# M.net
KiCad netlist of a schematic drawn in Altium Designer
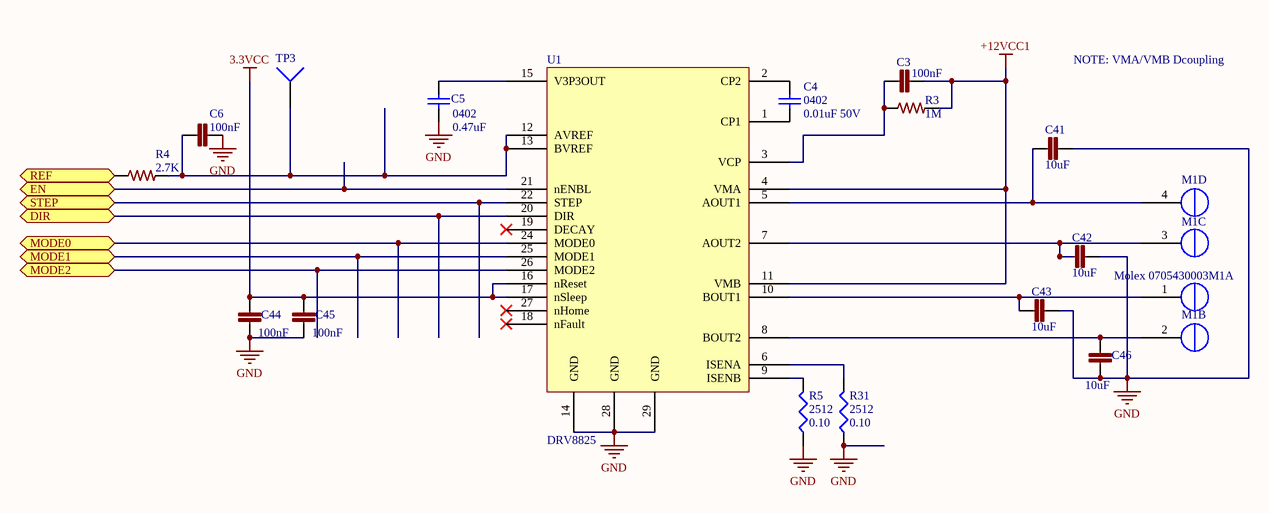
[diagram p0: M.SchDoc]

(export (version "E")
  (design (tool "Eeschema 10.0.6"))
  (components
    (comp (ref "C3")
      (value "100nF")
      (footprint "C0603")
      (description "CAP CER 0603 100nF 50V 10% X7R")
      (fields
        (field (name "MANUFACTURERPARTNUMBER") "C0603C104K5RACTU")
        (field (name "PUBLISHER") "UltiMachine")
      )
      (libsource (lib "3Delight") (part "C0603C104K5RACTU"))
    )
    (comp (ref "C4")
      (value "0.01uF 50V")
      (footprint "C0402")
      (description "CAP CER 10000PF 50V X7R 0402")
      (fields
        (field (name "MFR PART #") "GRM155R71H103JA88D")
        (field (name "MFR") "Murata")
        (field (name "PACKAGEREFERENCE") "0402")
        (field (name "PUBLISHER") "Ultimachine")
      )
      (libsource (lib "Tigershark3D") (part "GRM155R71H103JA88D"))
    )
    (comp (ref "C5")
      (value "0.47uF")
      (footprint "C0402")
      (description "0.47uF 6.3v C0402 - GRM155R60J474KE19D")
      (fields
        (field (name "MFR PART #") "GRM155R60J474KE19D")
        (field (name "MFR") "Murata")
        (field (name "PACKAGEREFERENCE") "0402")
        (field (name "PUBLISHER") "Ultimachine")
      )
      (libsource (lib "Tigershark3D") (part "GRM155R60J474KE19D"))
    )
    (comp (ref "C6")
      (value "100nF")
      (footprint "C0402")
      (description "CAP CER 0402 100nF 16V 10% X7R")
      (fields
        (field (name "MANUFACTURERPARTNUMBER") "GRM155R71C104KA88D")
        (field (name "PUBLISHER") "UltiMachine")
      )
      (libsource (lib "") (part "GRM155R71C104KA88D_1"))
    )
    (comp (ref "C41")
      (value "10uF")
      (footprint "C0603")
      (description "CAP CER 0603 1uF 10V Y5V")
      (fields
        (field (name "MANUFACTURERPARTNUMBER") "CC0603ZRY5V6BB105")
        (field (name "PUBLISHER") "UltiMachine")
      )
      (libsource (lib "Tigershark3D") (part "CC0603ZRY5V6BB105"))
    )
    (comp (ref "C42")
      (value "10uF")
      (footprint "C0603")
      (description "CAP CER 0603 1uF 10V Y5V")
      (fields
        (field (name "MANUFACTURERPARTNUMBER") "CC0603ZRY5V6BB105")
        (field (name "PUBLISHER") "UltiMachine")
      )
      (libsource (lib "Tigershark3D") (part "CC0603ZRY5V6BB105"))
    )
    (comp (ref "C43")
      (value "10uF")
      (footprint "C0603")
      (description "CAP CER 0603 1uF 10V Y5V")
      (fields
        (field (name "MANUFACTURERPARTNUMBER") "CC0603ZRY5V6BB105")
        (field (name "PUBLISHER") "UltiMachine")
      )
      (libsource (lib "Tigershark3D") (part "CC0603ZRY5V6BB105"))
    )
    (comp (ref "C44")
      (value "100nF")
      (footprint "C0402")
      (description "CAP CER 0402 100nF 16V 10% X7R")
      (fields
        (field (name "MANUFACTURERPARTNUMBER") "GRM155R71C104KA88D")
        (field (name "PUBLISHER") "UltiMachine")
      )
      (libsource (lib "3Delight") (part "GRM155R71C104KA88D"))
    )
    (comp (ref "C45")
      (value "100nF")
      (footprint "C0402")
      (description "CAP CER 0402 100nF 16V 10% X7R")
      (fields
        (field (name "MANUFACTURERPARTNUMBER") "GRM155R71C104KA88D")
        (field (name "PUBLISHER") "UltiMachine")
      )
      (libsource (lib "3Delight") (part "GRM155R71C104KA88D"))
    )
    (comp (ref "C46")
      (value "10uF")
      (footprint "C0603")
      (description "CAP CER 0603 1uF 10V Y5V")
      (fields
        (field (name "MANUFACTURERPARTNUMBER") "CC0603ZRY5V6BB105")
        (field (name "PUBLISHER") "UltiMachine")
      )
      (libsource (lib "") (part "CC0603ZRY5V6BB105_1"))
    )
    (comp (ref "M1")
      (value "Molex 0705430003")
      (footprint "4POL254")
      (description "Molex 4 Pin Clip Connector")
      (libsource (lib "ZMBo Schematic Library") (part "Molex 0705430003 Alt"))
    )
    (comp (ref "R3")
      (value "1M")
      (footprint "R0402")
      (description "RES 0402 1M 100mW 5%")
      (fields (field (name "MANUFACTURERPARTNUMBER") "ERJ2GEJ105X") (field (name "PUBLISHER") "UltiMachine"))
      (libsource (lib "Tigershark3D") (part "ERJ2GEJ105X"))
    )
    (comp (ref "R4")
      (value "2.7K")
      (footprint "R0402")
      (description "RES SMD 2.7K OHM 1% 1/10W 0402")
      (fields
        (field (name "MANUFACTURER") "Panasonic")
        (field (name "MANUFACTURERPARTNUMBER") "ERJ2GEJ105X")
        (field (name "PUBLISHER") "Adam")
      )
      (libsource (lib "Tigershark3D") (part "ERJ-2RKF2701X"))
    )
    (comp (ref "R5")
      (value "2512")
      (footprint "2512R-0.55")
      (description "RES SMD 0.1 OHM 1% 2W 2512")
      (fields (field (name "MFR") "Stackpole ELectronics Inc") (field (name "ALTIUM_VALUE") "0.10"))
      (libsource (lib "Tigershark3D") (part "CSRN2512FTR100"))
    )
    (comp (ref "R31")
      (value "2512")
      (footprint "2512R-0.55")
      (description "RES SMD 0.1 OHM 1% 2W 2512")
      (fields (field (name "MFR") "Stackpole ELectronics Inc") (field (name "ALTIUM_VALUE") "0.10"))
      (libsource (lib "Tigershark3D") (part "CSRN2512FTR100"))
    )
    (comp (ref "TP3")
      (value "TP4")
      (footprint "TP-2")
      (description "Socket")
      (fields (field (name "PUBLISHER") "Altium Limited"))
      (libsource (lib "ZMBo Schematic Library") (part "Socket"))
    )
    (comp (ref "U1")
      (value "DRV8825")
      (footprint "DRV8825PWPR")
      (description "DRV8825 Ti Stepper Driver")
      (fields (field (name "PART NUMBER") "DRV8825PWPR") (field (name "VOLTAGE") "8.2-45VDC"))
      (libsource (lib "Tigershark3D") (part "DRV8825"))
    )
  )
  (nets
    (net (code "1") (name "+12VCC1") (class "Default")
      (node (ref "C3") (pin "2") (pinfunction "2_2") (pintype "passive"))
      (node (ref "R3") (pin "2") (pinfunction "2_2") (pintype "passive"))
      (node (ref "U1") (pin "11") (pinfunction "VMB_11") (pintype "passive"))
      (node (ref "U1") (pin "4") (pinfunction "VMA_4") (pintype "passive"))
    )
    (net (code "2") (name "/DIR") (class "Default")
      (node (ref "U1") (pin "20") (pinfunction "DIR_20") (pintype "passive"))
    )
    (net (code "3") (name "/EN") (class "Default")
      (node (ref "U1") (pin "21") (pinfunction "nENBL_21") (pintype "passive"))
    )
    (net (code "4") (name "/MODE0") (class "Default")
      (node (ref "U1") (pin "24") (pinfunction "MODE0_24") (pintype "passive"))
    )
    (net (code "5") (name "/MODE1") (class "Default")
      (node (ref "U1") (pin "25") (pinfunction "MODE1_25") (pintype "passive"))
    )
    (net (code "6") (name "/MODE2") (class "Default")
      (node (ref "U1") (pin "26") (pinfunction "MODE2_26") (pintype "passive"))
    )
    (net (code "7") (name "/REF") (class "Default")
      (node (ref "R4") (pin "1") (pinfunction "1_1") (pintype "passive"))
    )
    (net (code "8") (name "/STEP") (class "Default")
      (node (ref "U1") (pin "22") (pinfunction "STEP_22") (pintype "passive"))
    )
    (net (code "9") (name "3.3VCC") (class "Default")
      (node (ref "C44") (pin "1") (pinfunction "1_1") (pintype "passive"))
      (node (ref "C45") (pin "1") (pinfunction "1_1") (pintype "passive"))
      (node (ref "U1") (pin "16") (pinfunction "nReset_16") (pintype "passive"))
      (node (ref "U1") (pin "17") (pinfunction "nSleep_17") (pintype "passive"))
    )
    (net (code "10") (name "GND") (class "Default")
      (node (ref "C41") (pin "2") (pinfunction "2_2") (pintype "passive"))
      (node (ref "C42") (pin "2") (pinfunction "2_2") (pintype "passive"))
      (node (ref "C43") (pin "2") (pinfunction "2_2") (pintype "passive"))
      (node (ref "C44") (pin "2") (pinfunction "2_2") (pintype "passive"))
      (node (ref "C45") (pin "2") (pinfunction "2_2") (pintype "passive"))
      (node (ref "C46") (pin "2") (pinfunction "2_2") (pintype "passive"))
      (node (ref "C5") (pin "1") (pinfunction "1_1") (pintype "passive"))
      (node (ref "C6") (pin "1") (pinfunction "1_1") (pintype "passive"))
      (node (ref "R31") (pin "1") (pinfunction "1_1") (pintype "passive"))
      (node (ref "R5") (pin "1") (pinfunction "1_1") (pintype "passive"))
      (node (ref "U1") (pin "14") (pinfunction "GND_14") (pintype "passive"))
      (node (ref "U1") (pin "28") (pinfunction "GND_28") (pintype "passive"))
      (node (ref "U1") (pin "29") (pinfunction "GND_29") (pintype "passive"))
    )
    (net (code "11") (name "Net-(M1A-OUT2B)") (class "Default")
      (node (ref "C43") (pin "1") (pinfunction "1_1") (pintype "passive"))
      (node (ref "M1") (pin "1") (pinfunction "OUT2B_1") (pintype "passive"))
      (node (ref "U1") (pin "10") (pinfunction "BOUT1_10") (pintype "passive"))
    )
    (net (code "12") (name "Net-(M1B-OUT2A)") (class "Default")
      (node (ref "C46") (pin "1") (pinfunction "1_1") (pintype "passive"))
      (node (ref "M1") (pin "2") (pinfunction "OUT2A_2") (pintype "passive"))
      (node (ref "U1") (pin "8") (pinfunction "BOUT2_8") (pintype "passive"))
    )
    (net (code "13") (name "Net-(M1C-OUT1A)") (class "Default")
      (node (ref "C42") (pin "1") (pinfunction "1_1") (pintype "passive"))
      (node (ref "M1") (pin "3") (pinfunction "OUT1A_3") (pintype "passive"))
      (node (ref "U1") (pin "7") (pinfunction "AOUT2_7") (pintype "passive"))
    )
    (net (code "14") (name "Net-(M1D-OUT1B)") (class "Default")
      (node (ref "C41") (pin "1") (pinfunction "1_1") (pintype "passive"))
      (node (ref "M1") (pin "4") (pinfunction "OUT1B_4") (pintype "passive"))
      (node (ref "U1") (pin "5") (pinfunction "AOUT1_5") (pintype "passive"))
    )
    (net (code "15") (name "Net-(U1-AVREF)") (class "Default")
      (node (ref "C6") (pin "2") (pinfunction "2_2") (pintype "passive"))
      (node (ref "R4") (pin "2") (pinfunction "2_2") (pintype "passive"))
      (node (ref "TP3") (pin "1") (pinfunction "1_1") (pintype "passive"))
      (node (ref "U1") (pin "12") (pinfunction "AVREF_12") (pintype "passive"))
      (node (ref "U1") (pin "13") (pinfunction "BVREF_13") (pintype "passive"))
    )
    (net (code "16") (name "Net-(U1-CP1)") (class "Default")
      (node (ref "C4") (pin "1") (pinfunction "1_1") (pintype "passive"))
      (node (ref "U1") (pin "1") (pinfunction "CP1_1") (pintype "passive"))
    )
    (net (code "17") (name "Net-(U1-CP2)") (class "Default")
      (node (ref "C4") (pin "2") (pinfunction "2_2") (pintype "passive"))
      (node (ref "U1") (pin "2") (pinfunction "CP2_2") (pintype "passive"))
    )
    (net (code "18") (name "Net-(U1-ISENA)") (class "Default")
      (node (ref "R31") (pin "2") (pinfunction "2_2") (pintype "passive"))
      (node (ref "U1") (pin "6") (pinfunction "ISENA_6") (pintype "passive"))
    )
    (net (code "19") (name "Net-(U1-ISENB)") (class "Default")
      (node (ref "R5") (pin "2") (pinfunction "2_2") (pintype "passive"))
      (node (ref "U1") (pin "9") (pinfunction "ISENB_9") (pintype "passive"))
    )
    (net (code "20") (name "Net-(U1-V3P3OUT)") (class "Default")
      (node (ref "C5") (pin "2") (pinfunction "2_2") (pintype "passive"))
      (node (ref "U1") (pin "15") (pinfunction "V3P3OUT_15") (pintype "passive"))
    )
    (net (code "21") (name "Net-(U1-VCP)") (class "Default")
      (node (ref "C3") (pin "1") (pinfunction "1_1") (pintype "passive"))
      (node (ref "R3") (pin "1") (pinfunction "1_1") (pintype "passive"))
      (node (ref "U1") (pin "3") (pinfunction "VCP_3") (pintype "passive"))
    )
    (net (code "22") (name "unconnected-(U1-DECAY-Pad19)") (class "Default")
      (node (ref "U1") (pin "19") (pinfunction "DECAY_19") (pintype "passive+no_connect"))
    )
    (net (code "23") (name "unconnected-(U1-NC-Pad23)") (class "Default")
      (node (ref "U1") (pin "23") (pinfunction "NC_23") (pintype "passive"))
    )
    (net (code "24") (name "unconnected-(U1-nFault-Pad18)") (class "Default")
      (node (ref "U1") (pin "18") (pinfunction "nFault_18") (pintype "passive+no_connect"))
    )
    (net (code "25") (name "unconnected-(U1-nHome-Pad27)") (class "Default")
      (node (ref "U1") (pin "27") (pinfunction "nHome_27") (pintype "passive+no_connect"))
    )
  )
)
